# XBee-Adapter_v10.net
KiCad netlist of a schematic drawn in EAGLE
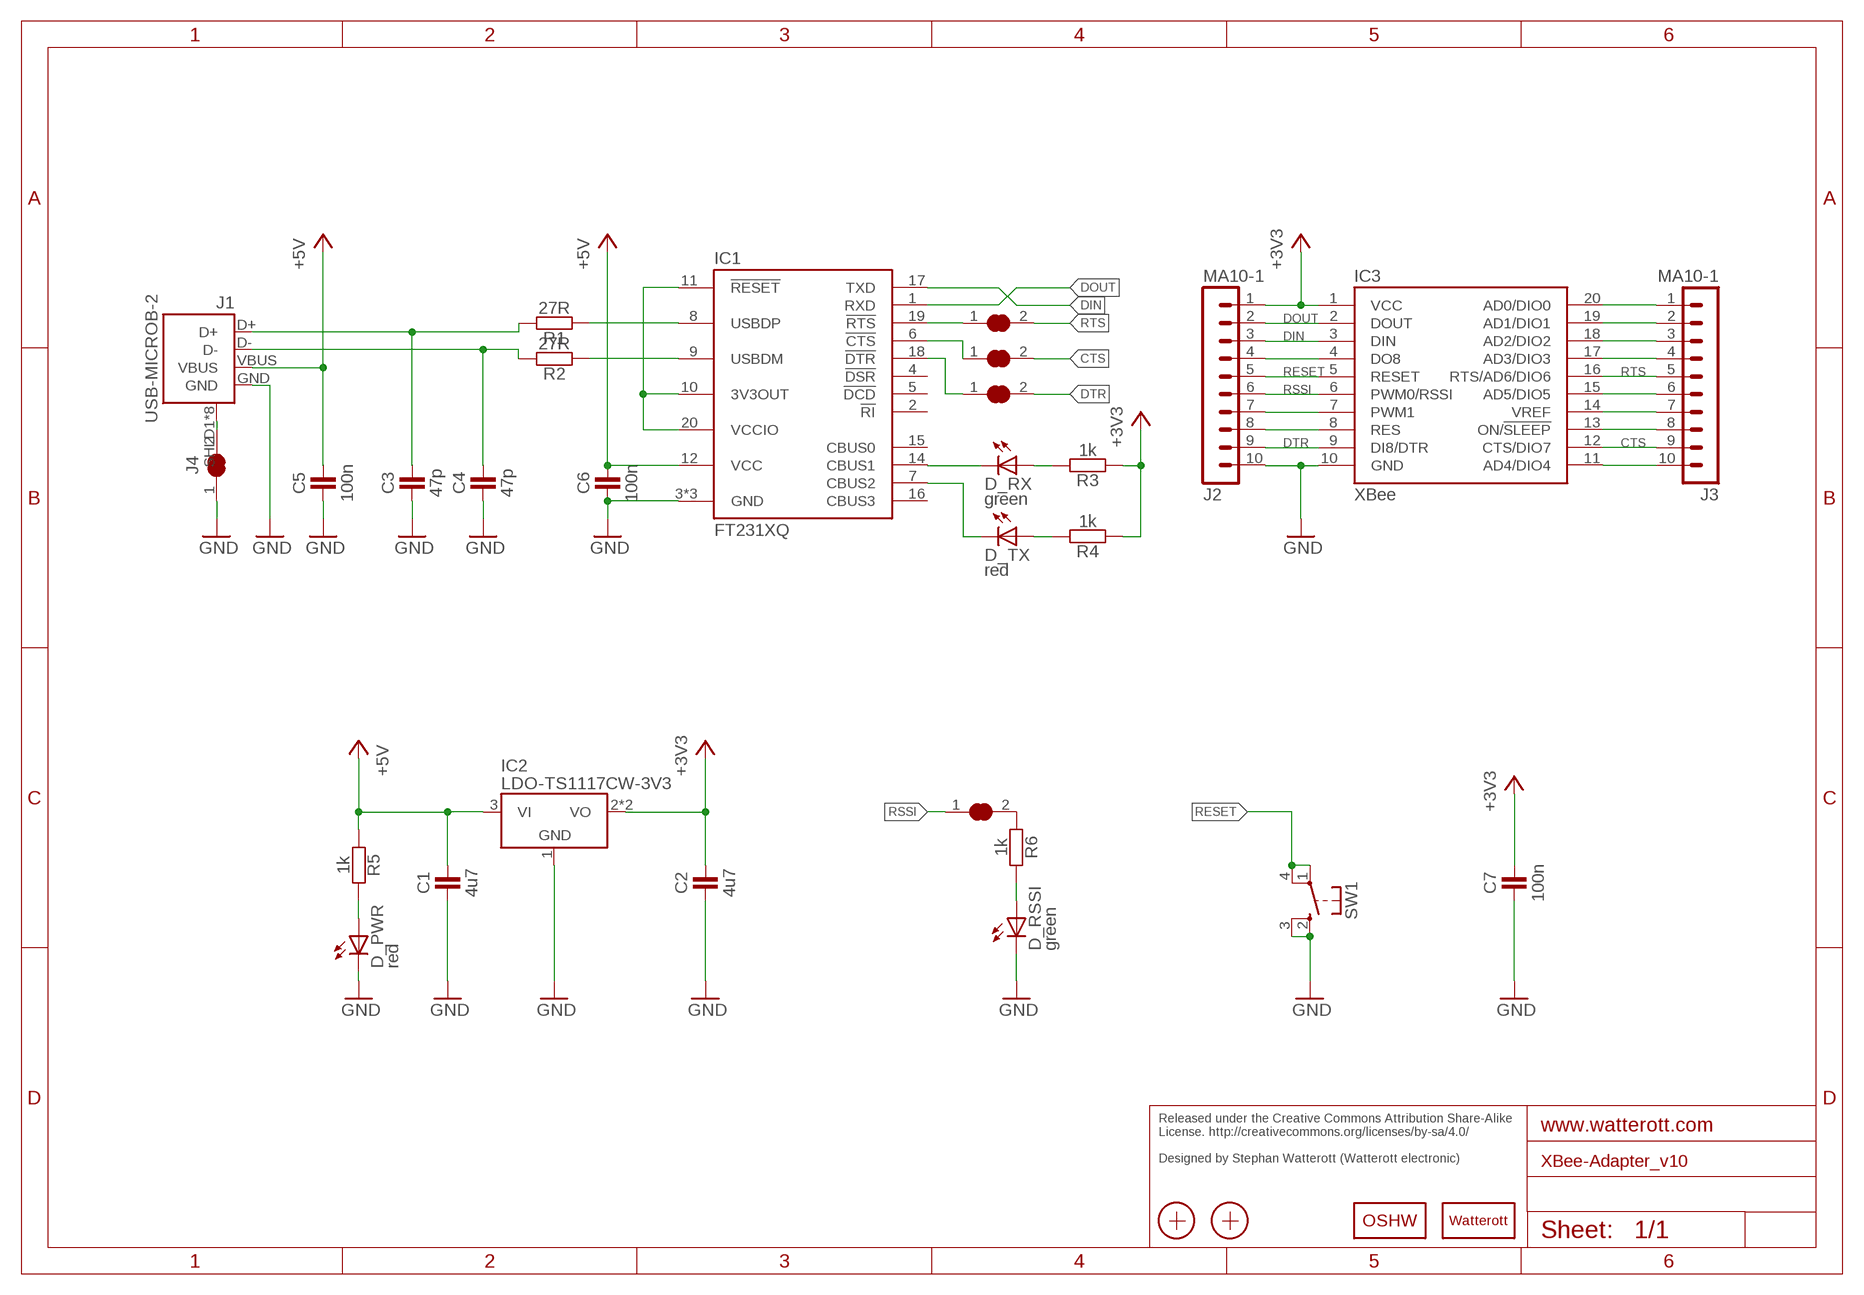
[diagram p0: schematic, sheet 1]

(export (version "E")
  (design (tool "Eeschema 10.0.6"))
  (components
    (comp (ref "C1")
      (value "4u7")
      (footprint "eagle-import:C0402")
      (libsource (lib "eagle-import") (part "CAPACITOR-0402"))
    )
    (comp (ref "C2")
      (value "4u7")
      (footprint "eagle-import:C0402")
      (libsource (lib "eagle-import") (part "CAPACITOR-0402"))
    )
    (comp (ref "C3")
      (value "47p")
      (footprint "eagle-import:C0402")
      (libsource (lib "eagle-import") (part "CAPACITOR-0402"))
    )
    (comp (ref "C4")
      (value "47p")
      (footprint "eagle-import:C0402")
      (libsource (lib "eagle-import") (part "CAPACITOR-0402"))
    )
    (comp (ref "C5")
      (value "100n")
      (footprint "eagle-import:C0402")
      (libsource (lib "eagle-import") (part "CAPACITOR-0402"))
    )
    (comp (ref "C6")
      (value "100n")
      (footprint "eagle-import:C0402")
      (libsource (lib "eagle-import") (part "CAPACITOR-0402"))
    )
    (comp (ref "C7")
      (value "100n")
      (footprint "eagle-import:C0402")
      (libsource (lib "eagle-import") (part "CAPACITOR-0402"))
    )
    (comp (ref "CTS")
      (value "JUMPER2-0603")
      (footprint "eagle-import:JUMPER2-0603")
      (libsource (lib "eagle-import") (part "JUMPER2-0603"))
    )
    (comp (ref "DTR")
      (value "JUMPER2-0603")
      (footprint "eagle-import:JUMPER2-0603")
      (libsource (lib "eagle-import") (part "JUMPER2-0603"))
    )
    (comp (ref "D_PWR")
      (value "red")
      (footprint "eagle-import:C0603")
      (libsource (lib "eagle-import") (part "LED-0603"))
    )
    (comp (ref "D_RSSI")
      (value "green")
      (footprint "eagle-import:C0603")
      (libsource (lib "eagle-import") (part "LED-0603"))
    )
    (comp (ref "D_RX")
      (value "green")
      (footprint "eagle-import:C0603")
      (libsource (lib "eagle-import") (part "LED-0603"))
    )
    (comp (ref "D_TX")
      (value "red")
      (footprint "eagle-import:C0603")
      (libsource (lib "eagle-import") (part "LED-0603"))
    )
    (comp (ref "IC1")
      (value "FT231XQ")
      (footprint "eagle-import:QFN20-PAD")
      (libsource (lib "eagle-import") (part "FT231XQ"))
    )
    (comp (ref "IC2")
      (value "LDO-TS1117CW-3V3")
      (footprint "eagle-import:SOT223")
      (libsource (lib "eagle-import") (part "LDO-TS1117CW-3V3"))
    )
    (comp (ref "IC3")
      (value "XBee")
      (footprint "eagle-import:XBEE")
      (libsource (lib "eagle-import") (part "XBEE"))
    )
    (comp (ref "J1")
      (value "USB-MICROB-2")
      (footprint "eagle-import:USB-MICROB-10118194")
      (libsource (lib "eagle-import") (part "USB-MICROB-2"))
    )
    (comp (ref "J2")
      (value "MA10-1")
      (footprint "eagle-import:MA10-1")
      (libsource (lib "eagle-import") (part "MA10-1"))
    )
    (comp (ref "J3")
      (value "MA10-1")
      (footprint "eagle-import:MA10-1")
      (libsource (lib "eagle-import") (part "MA10-1"))
    )
    (comp (ref "J4")
      (value "JUMPER2-0603")
      (footprint "eagle-import:JUMPER2-0603")
      (libsource (lib "eagle-import") (part "JUMPER2-0603"))
    )
    (comp (ref "LOGO1")
      (value "OSHW_LOGOX0150")
      (footprint "eagle-import:OSHW_6X150")
      (libsource (lib "eagle-import") (part "OSHW_LOGOX0150"))
    )
    (comp (ref "LOGO2")
      (value "LOGO-S_PLACE_M")
      (footprint "eagle-import:SPARK_TPLACE_M")
      (libsource (lib "eagle-import") (part "LOGO-S_PLACE_M"))
    )
    (comp (ref "R1")
      (value "27R")
      (footprint "eagle-import:C0402")
      (libsource (lib "eagle-import") (part "RESISTOR-0402"))
    )
    (comp (ref "R2")
      (value "27R")
      (footprint "eagle-import:C0402")
      (libsource (lib "eagle-import") (part "RESISTOR-0402"))
    )
    (comp (ref "R3")
      (value "1k")
      (footprint "eagle-import:C0402")
      (libsource (lib "eagle-import") (part "RESISTOR-0402"))
    )
    (comp (ref "R4")
      (value "1k")
      (footprint "eagle-import:C0402")
      (libsource (lib "eagle-import") (part "RESISTOR-0402"))
    )
    (comp (ref "R5")
      (value "1k")
      (footprint "eagle-import:C0402")
      (libsource (lib "eagle-import") (part "RESISTOR-0402"))
    )
    (comp (ref "R6")
      (value "1k")
      (footprint "eagle-import:C0402")
      (libsource (lib "eagle-import") (part "RESISTOR-0402"))
    )
    (comp (ref "RSSI")
      (value "JUMPER2-0603")
      (footprint "eagle-import:JUMPER2-0603")
      (libsource (lib "eagle-import") (part "JUMPER2-0603"))
    )
    (comp (ref "RTS")
      (value "JUMPER2-0603")
      (footprint "eagle-import:JUMPER2-0603")
      (libsource (lib "eagle-import") (part "JUMPER2-0603"))
    )
    (comp (ref "SW1")
      (value "SW-TACTILE-TL3315")
      (footprint "eagle-import:SW_TL3315N")
      (libsource (lib "eagle-import") (part "SW-TACTILE-TL3315"))
    )
    (comp (ref "X1")
      (value "PASSER-07")
      (footprint "eagle-import:PASSER_07MM")
      (libsource (lib "eagle-import") (part "PASSER-07"))
    )
    (comp (ref "X2")
      (value "PASSER-07")
      (footprint "eagle-import:PASSER_07MM")
      (libsource (lib "eagle-import") (part "PASSER-07"))
    )
  )
  (nets
    (net (code "1") (name "+3V3") (class "Default")
      (node (ref "C2") (pin "2") (pinfunction "2_2") (pintype "passive"))
      (node (ref "C7") (pin "2") (pinfunction "2_2") (pintype "passive"))
      (node (ref "IC2") (pin "2") (pinfunction "VO_2") (pintype "passive"))
      (node (ref "IC2") (pin "4") (pinfunction "VO_4") (pintype "passive"))
      (node (ref "IC3") (pin "1") (pinfunction "VCC_1") (pintype "power_in"))
      (node (ref "J2") (pin "1") (pinfunction "1_1") (pintype "passive"))
      (node (ref "R3") (pin "1") (pinfunction "1_1") (pintype "passive"))
      (node (ref "R4") (pin "1") (pinfunction "1_1") (pintype "passive"))
    )
    (net (code "2") (name "+5V") (class "Default")
      (node (ref "C1") (pin "2") (pinfunction "2_2") (pintype "passive"))
      (node (ref "C5") (pin "2") (pinfunction "2_2") (pintype "passive"))
      (node (ref "C6") (pin "2") (pinfunction "2_2") (pintype "passive"))
      (node (ref "IC1") (pin "12") (pinfunction "VCC_12") (pintype "power_in"))
      (node (ref "IC2") (pin "3") (pinfunction "VI_3") (pintype "input"))
      (node (ref "J1") (pin "VBUS") (pinfunction "VBUS_VBUS") (pintype "power_in"))
      (node (ref "R5") (pin "1") (pinfunction "1_1") (pintype "passive"))
    )
    (net (code "3") (name "CTS") (class "Default")
      (node (ref "CTS") (pin "2") (pinfunction "2_2") (pintype "passive"))
      (node (ref "IC3") (pin "12") (pinfunction "CTS/DIO7_12") (pintype "bidirectional"))
      (node (ref "J3") (pin "9") (pinfunction "9_9") (pintype "passive"))
    )
    (net (code "4") (name "DIN") (class "Default")
      (node (ref "IC1") (pin "17") (pinfunction "TXD_17") (pintype "bidirectional"))
      (node (ref "IC3") (pin "3") (pinfunction "DIN_3") (pintype "bidirectional"))
      (node (ref "J2") (pin "3") (pinfunction "3_3") (pintype "passive"))
    )
    (net (code "5") (name "DOUT") (class "Default")
      (node (ref "IC1") (pin "1") (pinfunction "RXD_1") (pintype "bidirectional"))
      (node (ref "IC3") (pin "2") (pinfunction "DOUT_2") (pintype "bidirectional"))
      (node (ref "J2") (pin "2") (pinfunction "2_2") (pintype "passive"))
    )
    (net (code "6") (name "DTR") (class "Default")
      (node (ref "DTR") (pin "2") (pinfunction "2_2") (pintype "passive"))
      (node (ref "IC3") (pin "9") (pinfunction "DI8/DTR_9") (pintype "bidirectional"))
      (node (ref "J2") (pin "9") (pinfunction "9_9") (pintype "passive"))
    )
    (net (code "7") (name "GND") (class "Default")
      (node (ref "C1") (pin "1") (pinfunction "1_1") (pintype "passive"))
      (node (ref "C2") (pin "1") (pinfunction "1_1") (pintype "passive"))
      (node (ref "C3") (pin "1") (pinfunction "1_1") (pintype "passive"))
      (node (ref "C4") (pin "1") (pinfunction "1_1") (pintype "passive"))
      (node (ref "C5") (pin "1") (pinfunction "1_1") (pintype "passive"))
      (node (ref "C6") (pin "1") (pinfunction "1_1") (pintype "passive"))
      (node (ref "C7") (pin "1") (pinfunction "1_1") (pintype "passive"))
      (node (ref "D_PWR") (pin "C") (pinfunction "C_C") (pintype "passive"))
      (node (ref "D_RSSI") (pin "C") (pinfunction "C_C") (pintype "passive"))
      (node (ref "IC1") (pin "13") (pinfunction "GND_13") (pintype "power_in"))
      (node (ref "IC1") (pin "3") (pinfunction "GND_3") (pintype "power_in"))
      (node (ref "IC1") (pin "TP") (pinfunction "GND_TP") (pintype "power_in"))
      (node (ref "IC2") (pin "1") (pinfunction "GND_1") (pintype "passive"))
      (node (ref "IC3") (pin "10") (pinfunction "GND_10") (pintype "power_in"))
      (node (ref "J1") (pin "GND") (pinfunction "GND_GND") (pintype "power_in"))
      (node (ref "J2") (pin "10") (pinfunction "10_10") (pintype "passive"))
      (node (ref "J4") (pin "1") (pinfunction "1_1") (pintype "passive"))
      (node (ref "SW1") (pin "2") (pinfunction "S1_2") (pintype "passive"))
      (node (ref "SW1") (pin "3") (pinfunction "S2_3") (pintype "passive"))
    )
    (net (code "8") (name "Net-(C3-Pad2)") (class "Default")
      (node (ref "C3") (pin "2") (pinfunction "2_2") (pintype "passive"))
      (node (ref "J1") (pin "D+") (pinfunction "D+_D+") (pintype "bidirectional"))
      (node (ref "R1") (pin "2") (pinfunction "2_2") (pintype "passive"))
    )
    (net (code "9") (name "Net-(C4-Pad2)") (class "Default")
      (node (ref "C4") (pin "2") (pinfunction "2_2") (pintype "passive"))
      (node (ref "J1") (pin "D-") (pinfunction "D-_D-") (pintype "bidirectional"))
      (node (ref "R2") (pin "2") (pinfunction "2_2") (pintype "passive"))
    )
    (net (code "10") (name "Net-(D_PWR-PadA)") (class "Default")
      (node (ref "D_PWR") (pin "A") (pinfunction "A_A") (pintype "passive"))
      (node (ref "R5") (pin "2") (pinfunction "2_2") (pintype "passive"))
    )
    (net (code "11") (name "Net-(D_RSSI-PadA)") (class "Default")
      (node (ref "D_RSSI") (pin "A") (pinfunction "A_A") (pintype "passive"))
      (node (ref "R6") (pin "2") (pinfunction "2_2") (pintype "passive"))
    )
    (net (code "12") (name "Net-(D_RX-PadA)") (class "Default")
      (node (ref "D_RX") (pin "A") (pinfunction "A_A") (pintype "passive"))
      (node (ref "R3") (pin "2") (pinfunction "2_2") (pintype "passive"))
    )
    (net (code "13") (name "Net-(D_TX-PadA)") (class "Default")
      (node (ref "D_TX") (pin "A") (pinfunction "A_A") (pintype "passive"))
      (node (ref "R4") (pin "2") (pinfunction "2_2") (pintype "passive"))
    )
    (net (code "14") (name "Net-(IC1-3V3OUT)") (class "Default")
      (node (ref "IC1") (pin "10") (pinfunction "3V3OUT_10") (pintype "power_in"))
      (node (ref "IC1") (pin "11") (pinfunction "~{RESET}_11") (pintype "bidirectional"))
      (node (ref "IC1") (pin "20") (pinfunction "VCCIO_20") (pintype "power_in"))
    )
    (net (code "15") (name "Net-(IC1-CBUS1)") (class "Default")
      (node (ref "D_RX") (pin "C") (pinfunction "C_C") (pintype "passive"))
      (node (ref "IC1") (pin "14") (pinfunction "CBUS1_14") (pintype "bidirectional"))
    )
    (net (code "16") (name "Net-(IC1-CBUS2)") (class "Default")
      (node (ref "D_TX") (pin "C") (pinfunction "C_C") (pintype "passive"))
      (node (ref "IC1") (pin "7") (pinfunction "CBUS2_7") (pintype "bidirectional"))
    )
    (net (code "17") (name "Net-(IC1-USBDM)") (class "Default")
      (node (ref "IC1") (pin "9") (pinfunction "USBDM_9") (pintype "bidirectional"))
      (node (ref "R2") (pin "1") (pinfunction "1_1") (pintype "passive"))
    )
    (net (code "18") (name "Net-(IC1-USBDP)") (class "Default")
      (node (ref "IC1") (pin "8") (pinfunction "USBDP_8") (pintype "bidirectional"))
      (node (ref "R1") (pin "1") (pinfunction "1_1") (pintype "passive"))
    )
    (net (code "19") (name "Net-(IC1-~{CTS})") (class "Default")
      (node (ref "CTS") (pin "1") (pinfunction "1_1") (pintype "passive"))
      (node (ref "IC1") (pin "6") (pinfunction "~{CTS}_6") (pintype "bidirectional"))
    )
    (net (code "20") (name "Net-(IC1-~{DTR})") (class "Default")
      (node (ref "DTR") (pin "1") (pinfunction "1_1") (pintype "passive"))
      (node (ref "IC1") (pin "18") (pinfunction "~{DTR}_18") (pintype "bidirectional"))
    )
    (net (code "21") (name "Net-(IC1-~{RTS})") (class "Default")
      (node (ref "IC1") (pin "19") (pinfunction "~{RTS}_19") (pintype "bidirectional"))
      (node (ref "RTS") (pin "1") (pinfunction "1_1") (pintype "passive"))
    )
    (net (code "22") (name "Net-(IC3-AD0{slash}DIO0)") (class "Default")
      (node (ref "IC3") (pin "20") (pinfunction "AD0/DIO0_20") (pintype "bidirectional"))
      (node (ref "J3") (pin "1") (pinfunction "1_1") (pintype "passive"))
    )
    (net (code "23") (name "Net-(IC3-AD1{slash}DIO1)") (class "Default")
      (node (ref "IC3") (pin "19") (pinfunction "AD1/DIO1_19") (pintype "bidirectional"))
      (node (ref "J3") (pin "2") (pinfunction "2_2") (pintype "passive"))
    )
    (net (code "24") (name "Net-(IC3-AD2{slash}DIO2)") (class "Default")
      (node (ref "IC3") (pin "18") (pinfunction "AD2/DIO2_18") (pintype "bidirectional"))
      (node (ref "J3") (pin "3") (pinfunction "3_3") (pintype "passive"))
    )
    (net (code "25") (name "Net-(IC3-AD3{slash}DIO3)") (class "Default")
      (node (ref "IC3") (pin "17") (pinfunction "AD3/DIO3_17") (pintype "bidirectional"))
      (node (ref "J3") (pin "4") (pinfunction "4_4") (pintype "passive"))
    )
    (net (code "26") (name "Net-(IC3-AD4{slash}DIO4)") (class "Default")
      (node (ref "IC3") (pin "11") (pinfunction "AD4/DIO4_11") (pintype "bidirectional"))
      (node (ref "J3") (pin "10") (pinfunction "10_10") (pintype "passive"))
    )
    (net (code "27") (name "Net-(IC3-AD5{slash}DIO5)") (class "Default")
      (node (ref "IC3") (pin "15") (pinfunction "AD5/DIO5_15") (pintype "bidirectional"))
      (node (ref "J3") (pin "6") (pinfunction "6_6") (pintype "passive"))
    )
    (net (code "28") (name "Net-(IC3-DO8)") (class "Default")
      (node (ref "IC3") (pin "4") (pinfunction "DO8_4") (pintype "bidirectional"))
      (node (ref "J2") (pin "4") (pinfunction "4_4") (pintype "passive"))
    )
    (net (code "29") (name "Net-(IC3-ON{slash}~{SLEEP})") (class "Default")
      (node (ref "IC3") (pin "13") (pinfunction "ON/~{SLEEP}_13") (pintype "bidirectional"))
      (node (ref "J3") (pin "8") (pinfunction "8_8") (pintype "passive"))
    )
    (net (code "30") (name "Net-(IC3-PWM1)") (class "Default")
      (node (ref "IC3") (pin "7") (pinfunction "PWM1_7") (pintype "bidirectional"))
      (node (ref "J2") (pin "7") (pinfunction "7_7") (pintype "passive"))
    )
    (net (code "31") (name "Net-(IC3-RES)") (class "Default")
      (node (ref "IC3") (pin "8") (pinfunction "RES_8") (pintype "bidirectional"))
      (node (ref "J2") (pin "8") (pinfunction "8_8") (pintype "passive"))
    )
    (net (code "32") (name "Net-(IC3-VREF)") (class "Default")
      (node (ref "IC3") (pin "14") (pinfunction "VREF_14") (pintype "bidirectional"))
      (node (ref "J3") (pin "7") (pinfunction "7_7") (pintype "passive"))
    )
    (net (code "33") (name "Net-(J1-SHIELD-PadSHLD1)") (class "Default")
      (node (ref "J1") (pin "SHLD1") (pinfunction "SHIELD_SHLD1") (pintype "passive"))
      (node (ref "J1") (pin "SHLD2") (pinfunction "SHIELD_SHLD2") (pintype "passive"))
      (node (ref "J1") (pin "SHLD3") (pinfunction "SHIELD_SHLD3") (pintype "passive"))
      (node (ref "J1") (pin "SHLD4") (pinfunction "SHIELD_SHLD4") (pintype "passive"))
      (node (ref "J1") (pin "SHLD5") (pinfunction "SHIELD_SHLD5") (pintype "passive"))
      (node (ref "J1") (pin "SHLD6") (pinfunction "SHIELD_SHLD6") (pintype "passive"))
      (node (ref "J1") (pin "SHLD7") (pinfunction "SHIELD_SHLD7") (pintype "passive"))
      (node (ref "J1") (pin "SHLD8") (pinfunction "SHIELD_SHLD8") (pintype "passive"))
      (node (ref "J4") (pin "2") (pinfunction "2_2") (pintype "passive"))
    )
    (net (code "34") (name "Net-(R6-Pad1)") (class "Default")
      (node (ref "R6") (pin "1") (pinfunction "1_1") (pintype "passive"))
      (node (ref "RSSI") (pin "2") (pinfunction "2_2") (pintype "passive"))
    )
    (net (code "35") (name "RESET") (class "Default")
      (node (ref "IC3") (pin "5") (pinfunction "RESET_5") (pintype "bidirectional"))
      (node (ref "J2") (pin "5") (pinfunction "5_5") (pintype "passive"))
      (node (ref "SW1") (pin "1") (pinfunction "P1_1") (pintype "passive"))
      (node (ref "SW1") (pin "4") (pinfunction "P2_4") (pintype "passive"))
    )
    (net (code "36") (name "RSSI") (class "Default")
      (node (ref "IC3") (pin "6") (pinfunction "PWM0/RSSI_6") (pintype "bidirectional"))
      (node (ref "J2") (pin "6") (pinfunction "6_6") (pintype "passive"))
      (node (ref "RSSI") (pin "1") (pinfunction "1_1") (pintype "passive"))
    )
    (net (code "37") (name "RTS") (class "Default")
      (node (ref "IC3") (pin "16") (pinfunction "RTS/AD6/DIO6_16") (pintype "bidirectional"))
      (node (ref "J3") (pin "5") (pinfunction "5_5") (pintype "passive"))
      (node (ref "RTS") (pin "2") (pinfunction "2_2") (pintype "passive"))
    )
    (net (code "38") (name "unconnected-(IC1-CBUS0-Pad15)") (class "Default")
      (node (ref "IC1") (pin "15") (pinfunction "CBUS0_15") (pintype "bidirectional"))
    )
    (net (code "39") (name "unconnected-(IC1-CBUS3-Pad16)") (class "Default")
      (node (ref "IC1") (pin "16") (pinfunction "CBUS3_16") (pintype "bidirectional"))
    )
    (net (code "40") (name "unconnected-(IC1-~{DCD}-Pad5)") (class "Default")
      (node (ref "IC1") (pin "5") (pinfunction "~{DCD}_5") (pintype "bidirectional"))
    )
    (net (code "41") (name "unconnected-(IC1-~{DSR}-Pad4)") (class "Default")
      (node (ref "IC1") (pin "4") (pinfunction "~{DSR}_4") (pintype "bidirectional"))
    )
    (net (code "42") (name "unconnected-(IC1-~{RI}-Pad2)") (class "Default")
      (node (ref "IC1") (pin "2") (pinfunction "~{RI}_2") (pintype "bidirectional"))
    )
  )
)
